# m303-stereo-output.net
KiCad netlist of a schematic drawn in EAGLE
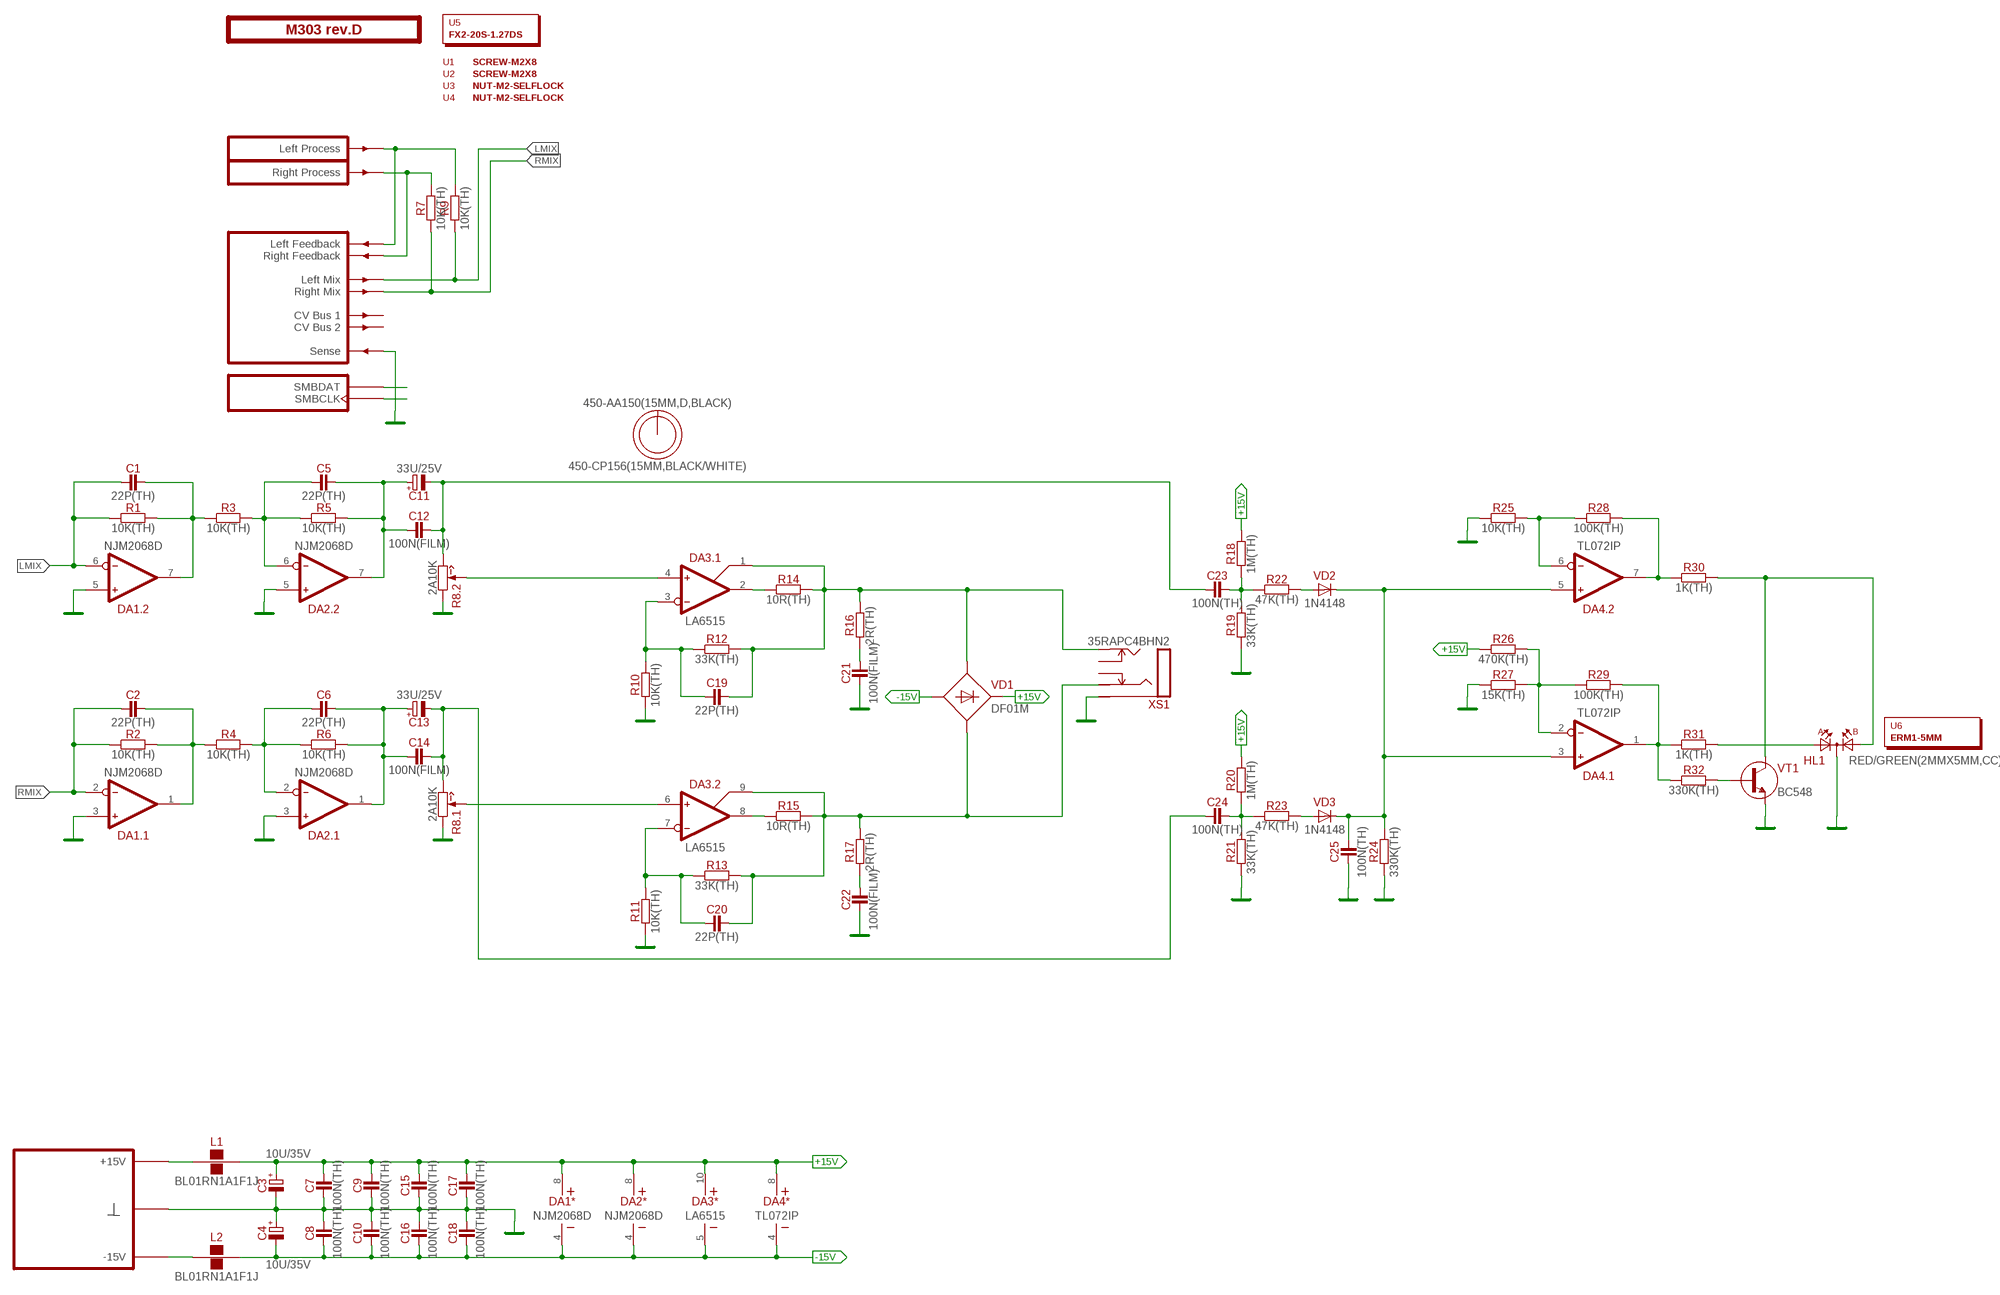
[diagram p0: schematic, sheet 1]

(export (version "E")
  (design (tool "Eeschema 10.0.6"))
  (components
    (comp (ref "C1")
      (value "22P(TH)")
      (footprint "eagle-import:C050-024X044")
      (libsource (lib "eagle-import") (part "?22P(TH)"))
    )
    (comp (ref "C2")
      (value "22P(TH)")
      (footprint "eagle-import:C050-024X044")
      (libsource (lib "eagle-import") (part "?22P(TH)"))
    )
    (comp (ref "C3")
      (value "10U/35V")
      (footprint "eagle-import:E2-5")
      (libsource (lib "eagle-import") (part "?10U/35V"))
    )
    (comp (ref "C4")
      (value "10U/35V")
      (footprint "eagle-import:E2-5")
      (libsource (lib "eagle-import") (part "?10U/35V"))
    )
    (comp (ref "C5")
      (value "22P(TH)")
      (footprint "eagle-import:C050-024X044")
      (libsource (lib "eagle-import") (part "?22P(TH)"))
    )
    (comp (ref "C6")
      (value "22P(TH)")
      (footprint "eagle-import:C050-024X044")
      (libsource (lib "eagle-import") (part "?22P(TH)"))
    )
    (comp (ref "C7")
      (value "100N(TH)")
      (footprint "eagle-import:C050-024X044")
      (libsource (lib "eagle-import") (part "?100N(TH)"))
    )
    (comp (ref "C8")
      (value "100N(TH)")
      (footprint "eagle-import:C050-024X044")
      (libsource (lib "eagle-import") (part "?100N(TH)"))
    )
    (comp (ref "C9")
      (value "100N(TH)")
      (footprint "eagle-import:C050-024X044")
      (libsource (lib "eagle-import") (part "?100N(TH)"))
    )
    (comp (ref "C10")
      (value "100N(TH)")
      (footprint "eagle-import:C050-024X044")
      (libsource (lib "eagle-import") (part "?100N(TH)"))
    )
    (comp (ref "C11")
      (value "33U/25V")
      (footprint "eagle-import:E2,5-7")
      (libsource (lib "eagle-import") (part "?33U/25V"))
    )
    (comp (ref "C12")
      (value "100N(FILM)")
      (footprint "eagle-import:C050-025X075")
      (libsource (lib "eagle-import") (part "?100N(FILM)"))
    )
    (comp (ref "C13")
      (value "33U/25V")
      (footprint "eagle-import:E2,5-7")
      (libsource (lib "eagle-import") (part "?33U/25V"))
    )
    (comp (ref "C14")
      (value "100N(FILM)")
      (footprint "eagle-import:C050-025X075")
      (libsource (lib "eagle-import") (part "?100N(FILM)"))
    )
    (comp (ref "C15")
      (value "100N(TH)")
      (footprint "eagle-import:C050-024X044")
      (libsource (lib "eagle-import") (part "?100N(TH)"))
    )
    (comp (ref "C16")
      (value "100N(TH)")
      (footprint "eagle-import:C050-024X044")
      (libsource (lib "eagle-import") (part "?100N(TH)"))
    )
    (comp (ref "C17")
      (value "100N(TH)")
      (footprint "eagle-import:C050-024X044")
      (libsource (lib "eagle-import") (part "?100N(TH)"))
    )
    (comp (ref "C18")
      (value "100N(TH)")
      (footprint "eagle-import:C050-024X044")
      (libsource (lib "eagle-import") (part "?100N(TH)"))
    )
    (comp (ref "C19")
      (value "22P(TH)")
      (footprint "eagle-import:C050-024X044")
      (libsource (lib "eagle-import") (part "?22P(TH)"))
    )
    (comp (ref "C20")
      (value "22P(TH)")
      (footprint "eagle-import:C050-024X044")
      (libsource (lib "eagle-import") (part "?22P(TH)"))
    )
    (comp (ref "C21")
      (value "100N(FILM)")
      (footprint "eagle-import:C050-025X075")
      (libsource (lib "eagle-import") (part "?100N(FILM)"))
    )
    (comp (ref "C22")
      (value "100N(FILM)")
      (footprint "eagle-import:C050-025X075")
      (libsource (lib "eagle-import") (part "?100N(FILM)"))
    )
    (comp (ref "C23")
      (value "100N(TH)")
      (footprint "eagle-import:C050-024X044")
      (libsource (lib "eagle-import") (part "?100N(TH)"))
    )
    (comp (ref "C24")
      (value "100N(TH)")
      (footprint "eagle-import:C050-024X044")
      (libsource (lib "eagle-import") (part "?100N(TH)"))
    )
    (comp (ref "C25")
      (value "100N(TH)")
      (footprint "eagle-import:C050-024X044")
      (libsource (lib "eagle-import") (part "?100N(TH)"))
    )
    (comp (ref "DA1")
      (value "NJM2068D")
      (footprint "eagle-import:DIP-8")
      (libsource (lib "eagle-import") (part "NJM2068D"))
    )
    (comp (ref "DA2")
      (value "NJM2068D")
      (footprint "eagle-import:DIP-8")
      (libsource (lib "eagle-import") (part "NJM2068D"))
    )
    (comp (ref "DA3")
      (value "LA6515")
      (footprint "eagle-import:SIL10")
      (libsource (lib "eagle-import") (part "LA6515"))
    )
    (comp (ref "DA4")
      (value "TL072IP")
      (footprint "eagle-import:DIP-8")
      (libsource (lib "eagle-import") (part "TL072IP"))
    )
    (comp (ref "HL1")
      (value "RED/GREEN(2MMX5MM,CC)")
      (footprint "eagle-import:LED2X5-3PIN")
      (libsource (lib "eagle-import") (part "?(2MMX5MM,CC)RED/GREEN"))
    )
    (comp (ref "L1")
      (value "BL01RN1A1F1J")
      (footprint "eagle-import:BL01RN1A")
      (libsource (lib "eagle-import") (part "BL01RN1A?1F1J"))
    )
    (comp (ref "L2")
      (value "BL01RN1A1F1J")
      (footprint "eagle-import:BL01RN1A")
      (libsource (lib "eagle-import") (part "BL01RN1A?1F1J"))
    )
    (comp (ref "O1")
      (value "450-AA150(15MM,D,BLACK)")
      (footprint "eagle-import:EMPTY")
      (libsource (lib "eagle-import") (part "450-AA?150(15MM,D,BLACK)"))
    )
    (comp (ref "O2")
      (value "450-CP156(15MM,BLACK/WHITE)")
      (footprint "eagle-import:EMPTY")
      (libsource (lib "eagle-import") (part "450-C?P156(15MM,BLACK/WHITE)"))
    )
    (comp (ref "PCB1")
      (value "M303 rev.D")
      (footprint "eagle-import:ST2-BOARD-50-END")
      (libsource (lib "eagle-import") (part "ST2-BOARD-50-END"))
    )
    (comp (ref "R1")
      (value "10K(TH)")
      (footprint "eagle-import:R-0207_10")
      (libsource (lib "eagle-import") (part "?10K(TH)"))
    )
    (comp (ref "R2")
      (value "10K(TH)")
      (footprint "eagle-import:R-0207_10")
      (libsource (lib "eagle-import") (part "?10K(TH)"))
    )
    (comp (ref "R3")
      (value "10K(TH)")
      (footprint "eagle-import:R-0207_10")
      (libsource (lib "eagle-import") (part "?10K(TH)"))
    )
    (comp (ref "R4")
      (value "10K(TH)")
      (footprint "eagle-import:R-0207_10")
      (libsource (lib "eagle-import") (part "?10K(TH)"))
    )
    (comp (ref "R5")
      (value "10K(TH)")
      (footprint "eagle-import:R-0207_10")
      (libsource (lib "eagle-import") (part "?10K(TH)"))
    )
    (comp (ref "R6")
      (value "10K(TH)")
      (footprint "eagle-import:R-0207_10")
      (libsource (lib "eagle-import") (part "?10K(TH)"))
    )
    (comp (ref "R7")
      (value "10K(TH)")
      (footprint "eagle-import:R-0207_10")
      (libsource (lib "eagle-import") (part "?10K(TH)"))
    )
    (comp (ref "R8")
      (value "2A10K")
      (footprint "eagle-import:RV11-DUAL")
      (libsource (lib "eagle-import") (part "2?A10K"))
    )
    (comp (ref "R9")
      (value "10K(TH)")
      (footprint "eagle-import:R-0207_10")
      (libsource (lib "eagle-import") (part "?10K(TH)"))
    )
    (comp (ref "R10")
      (value "10K(TH)")
      (footprint "eagle-import:R-0207_10")
      (libsource (lib "eagle-import") (part "?10K(TH)"))
    )
    (comp (ref "R11")
      (value "10K(TH)")
      (footprint "eagle-import:R-0207_10")
      (libsource (lib "eagle-import") (part "?10K(TH)"))
    )
    (comp (ref "R12")
      (value "33K(TH)")
      (footprint "eagle-import:R-0207_10")
      (libsource (lib "eagle-import") (part "?33K(TH)"))
    )
    (comp (ref "R13")
      (value "33K(TH)")
      (footprint "eagle-import:R-0207_10")
      (libsource (lib "eagle-import") (part "?33K(TH)"))
    )
    (comp (ref "R14")
      (value "10R(TH)")
      (footprint "eagle-import:R-0207_10")
      (libsource (lib "eagle-import") (part "?10R(TH)"))
    )
    (comp (ref "R15")
      (value "10R(TH)")
      (footprint "eagle-import:R-0207_10")
      (libsource (lib "eagle-import") (part "?10R(TH)"))
    )
    (comp (ref "R16")
      (value "2R(TH)")
      (footprint "eagle-import:R-0207_10")
      (libsource (lib "eagle-import") (part "?2R(TH)"))
    )
    (comp (ref "R17")
      (value "2R(TH)")
      (footprint "eagle-import:R-0207_10")
      (libsource (lib "eagle-import") (part "?2R(TH)"))
    )
    (comp (ref "R18")
      (value "1M(TH)")
      (footprint "eagle-import:R-0207_10")
      (libsource (lib "eagle-import") (part "?1M(TH)"))
    )
    (comp (ref "R19")
      (value "33K(TH)")
      (footprint "eagle-import:R-0207_10")
      (libsource (lib "eagle-import") (part "?33K(TH)"))
    )
    (comp (ref "R20")
      (value "1M(TH)")
      (footprint "eagle-import:R-0207_10")
      (libsource (lib "eagle-import") (part "?1M(TH)"))
    )
    (comp (ref "R21")
      (value "33K(TH)")
      (footprint "eagle-import:R-0207_10")
      (libsource (lib "eagle-import") (part "?33K(TH)"))
    )
    (comp (ref "R22")
      (value "47K(TH)")
      (footprint "eagle-import:R-0207_10")
      (libsource (lib "eagle-import") (part "?47K(TH)"))
    )
    (comp (ref "R23")
      (value "47K(TH)")
      (footprint "eagle-import:R-0207_10")
      (libsource (lib "eagle-import") (part "?47K(TH)"))
    )
    (comp (ref "R24")
      (value "330K(TH)")
      (footprint "eagle-import:R-0207_10")
      (libsource (lib "eagle-import") (part "?330K(TH)"))
    )
    (comp (ref "R25")
      (value "10K(TH)")
      (footprint "eagle-import:R-0207_10")
      (libsource (lib "eagle-import") (part "?10K(TH)"))
    )
    (comp (ref "R26")
      (value "470K(TH)")
      (footprint "eagle-import:R-0207_10")
      (libsource (lib "eagle-import") (part "?470K(TH)"))
    )
    (comp (ref "R27")
      (value "15K(TH)")
      (footprint "eagle-import:R-0207_10")
      (libsource (lib "eagle-import") (part "?15K(TH)"))
    )
    (comp (ref "R28")
      (value "100K(TH)")
      (footprint "eagle-import:R-0207_10")
      (libsource (lib "eagle-import") (part "?100K(TH)"))
    )
    (comp (ref "R29")
      (value "100K(TH)")
      (footprint "eagle-import:R-0207_10")
      (libsource (lib "eagle-import") (part "?100K(TH)"))
    )
    (comp (ref "R30")
      (value "1K(TH)")
      (footprint "eagle-import:R-0207_10")
      (libsource (lib "eagle-import") (part "?1K(TH)"))
    )
    (comp (ref "R31")
      (value "1K(TH)")
      (footprint "eagle-import:R-0207_10")
      (libsource (lib "eagle-import") (part "?1K(TH)"))
    )
    (comp (ref "R32")
      (value "330K(TH)")
      (footprint "eagle-import:R-0207_10")
      (libsource (lib "eagle-import") (part "?330K(TH)"))
    )
    (comp (ref "U1")
      (value "SCREW-M2X8")
      (footprint "eagle-import:EMPTY")
      (libsource (lib "eagle-import") (part "?SCREW-M2X8"))
    )
    (comp (ref "U2")
      (value "SCREW-M2X8")
      (footprint "eagle-import:EMPTY")
      (libsource (lib "eagle-import") (part "?SCREW-M2X8"))
    )
    (comp (ref "U3")
      (value "NUT-M2-SELFLOCK")
      (footprint "eagle-import:EMPTY")
      (libsource (lib "eagle-import") (part "?NUT-M2-SELFLOCK"))
    )
    (comp (ref "U4")
      (value "NUT-M2-SELFLOCK")
      (footprint "eagle-import:EMPTY")
      (libsource (lib "eagle-import") (part "?NUT-M2-SELFLOCK"))
    )
    (comp (ref "U5")
      (value "FX2-20S-1.27DS")
      (footprint "eagle-import:EMPTY")
      (libsource (lib "eagle-import") (part "?FX2-20S-1.27DS"))
    )
    (comp (ref "U6")
      (value "ERM1-5MM")
      (footprint "eagle-import:EMPTY")
      (libsource (lib "eagle-import") (part "?ERM1-5MM"))
    )
    (comp (ref "VD1")
      (value "DF01M")
      (footprint "eagle-import:MDIP-4")
      (libsource (lib "eagle-import") (part "DF?M01"))
    )
    (comp (ref "VD2")
      (value "1N4148")
      (footprint "eagle-import:DO35-7")
      (libsource (lib "eagle-import") (part "?1N4148"))
    )
    (comp (ref "VD3")
      (value "1N4148")
      (footprint "eagle-import:DO35-7")
      (libsource (lib "eagle-import") (part "?1N4148"))
    )
    (comp (ref "VT1")
      (value "BC548")
      (footprint "eagle-import:TO92")
      (libsource (lib "eagle-import") (part "?BC548"))
    )
    (comp (ref "XS1")
      (value "35RAPC4BHN2")
      (footprint "eagle-import:35RAP")
      (libsource (lib "eagle-import") (part "35RAPC4BHN2"))
    )
  )
  (nets
    (net (code "1") (name "+15V") (class "Default")
      (node (ref "C15") (pin "2") (pinfunction "2_2") (pintype "passive"))
      (node (ref "C17") (pin "2") (pinfunction "2_2") (pintype "passive"))
      (node (ref "C3") (pin "+") (pinfunction "+_+") (pintype "passive"))
      (node (ref "C7") (pin "2") (pinfunction "2_2") (pintype "passive"))
      (node (ref "C9") (pin "2") (pinfunction "2_2") (pintype "passive"))
      (node (ref "DA1") (pin "8") (pinfunction "V+_8") (pintype "power_in"))
      (node (ref "DA2") (pin "8") (pinfunction "V+_8") (pintype "power_in"))
      (node (ref "DA3") (pin "10") (pinfunction "V+_10") (pintype "power_in"))
      (node (ref "DA4") (pin "8") (pinfunction "V+_8") (pintype "power_in"))
      (node (ref "L1") (pin "2") (pinfunction "2_2") (pintype "passive"))
      (node (ref "R18") (pin "2") (pinfunction "2_2") (pintype "passive"))
      (node (ref "R20") (pin "2") (pinfunction "2_2") (pintype "passive"))
      (node (ref "R26") (pin "1") (pinfunction "1_1") (pintype "passive"))
      (node (ref "VD1") (pin "3") (pinfunction "C_3") (pintype "passive"))
    )
    (net (code "2") (name "-15V") (class "Default")
      (node (ref "C10") (pin "1") (pinfunction "1_1") (pintype "passive"))
      (node (ref "C16") (pin "1") (pinfunction "1_1") (pintype "passive"))
      (node (ref "C18") (pin "1") (pinfunction "1_1") (pintype "passive"))
      (node (ref "C4") (pin "-") (pinfunction "-_-") (pintype "passive"))
      (node (ref "C8") (pin "1") (pinfunction "1_1") (pintype "passive"))
      (node (ref "DA1") (pin "4") (pinfunction "V-_4") (pintype "power_in"))
      (node (ref "DA2") (pin "4") (pinfunction "V-_4") (pintype "power_in"))
      (node (ref "DA3") (pin "5") (pinfunction "V-_5") (pintype "power_in"))
      (node (ref "DA4") (pin "4") (pinfunction "V-_4") (pintype "power_in"))
      (node (ref "L2") (pin "2") (pinfunction "2_2") (pintype "passive"))
      (node (ref "VD1") (pin "4") (pinfunction "A_4") (pintype "passive"))
    )
    (net (code "3") (name "GND") (class "Default")
      (node (ref "C10") (pin "2") (pinfunction "2_2") (pintype "passive"))
      (node (ref "C15") (pin "1") (pinfunction "1_1") (pintype "passive"))
      (node (ref "C16") (pin "2") (pinfunction "2_2") (pintype "passive"))
      (node (ref "C17") (pin "1") (pinfunction "1_1") (pintype "passive"))
      (node (ref "C18") (pin "2") (pinfunction "2_2") (pintype "passive"))
      (node (ref "C21") (pin "1") (pinfunction "1_1") (pintype "passive"))
      (node (ref "C22") (pin "1") (pinfunction "1_1") (pintype "passive"))
      (node (ref "C25") (pin "1") (pinfunction "1_1") (pintype "passive"))
      (node (ref "C3") (pin "-") (pinfunction "-_-") (pintype "passive"))
      (node (ref "C4") (pin "+") (pinfunction "+_+") (pintype "passive"))
      (node (ref "C7") (pin "1") (pinfunction "1_1") (pintype "passive"))
      (node (ref "C8") (pin "2") (pinfunction "2_2") (pintype "passive"))
      (node (ref "C9") (pin "1") (pinfunction "1_1") (pintype "passive"))
      (node (ref "DA1") (pin "3") (pinfunction "IN+_3") (pintype "input"))
      (node (ref "DA1") (pin "5") (pinfunction "IN+_5") (pintype "input"))
      (node (ref "DA2") (pin "3") (pinfunction "IN+_3") (pintype "input"))
      (node (ref "DA2") (pin "5") (pinfunction "IN+_5") (pintype "input"))
      (node (ref "HL1") (pin "K") (pinfunction "K_K") (pintype "passive"))
      (node (ref "PCB1") (pin "B4") (pinfunction "GND_B4") (pintype "bidirectional"))
      (node (ref "PCB1") (pin "B5") (pinfunction "GND_B5") (pintype "bidirectional"))
      (node (ref "PCB1") (pin "B6") (pinfunction "GND_B6") (pintype "bidirectional"))
      (node (ref "PCB1") (pin "B7") (pinfunction "GND_B7") (pintype "bidirectional"))
      (node (ref "PCB1") (pin "B8") (pinfunction "GND_B8") (pintype "bidirectional"))
      (node (ref "PCB1") (pin "BSENSE") (pinfunction "SENSE_BSENSE") (pintype "bidirectional"))
      (node (ref "R10") (pin "1") (pinfunction "1_1") (pintype "passive"))
      (node (ref "R11") (pin "1") (pinfunction "1_1") (pintype "passive"))
      (node (ref "R19") (pin "1") (pinfunction "1_1") (pintype "passive"))
      (node (ref "R21") (pin "1") (pinfunction "1_1") (pintype "passive"))
      (node (ref "R24") (pin "1") (pinfunction "1_1") (pintype "passive"))
      (node (ref "R25") (pin "1") (pinfunction "1_1") (pintype "passive"))
      (node (ref "R27") (pin "1") (pinfunction "1_1") (pintype "passive"))
      (node (ref "R8") (pin "1") (pinfunction "CCW_1") (pintype "passive"))
      (node (ref "R8") (pin "1'") (pinfunction "CCW_1'") (pintype "passive"))
      (node (ref "VT1") (pin "3") (pinfunction "E_3") (pintype "passive"))
      (node (ref "XS1") (pin "1") (pinfunction "S_1") (pintype "passive"))
    )
    (net (code "4") (name "LMIX") (class "Default")
      (node (ref "C1") (pin "1") (pinfunction "1_1") (pintype "passive"))
      (node (ref "DA1") (pin "6") (pinfunction "IN-_6") (pintype "input"))
      (node (ref "PCB1") (pin "ALMIX") (pinfunction "LMIX_ALMIX") (pintype "bidirectional"))
      (node (ref "R1") (pin "1") (pinfunction "1_1") (pintype "passive"))
      (node (ref "R9") (pin "1") (pinfunction "1_1") (pintype "passive"))
    )
    (net (code "5") (name "Net-(C21-Pad2)") (class "Default")
      (node (ref "C21") (pin "2") (pinfunction "2_2") (pintype "passive"))
      (node (ref "R16") (pin "1") (pinfunction "1_1") (pintype "passive"))
    )
    (net (code "6") (name "Net-(C22-Pad2)") (class "Default")
      (node (ref "C22") (pin "2") (pinfunction "2_2") (pintype "passive"))
      (node (ref "R17") (pin "1") (pinfunction "1_1") (pintype "passive"))
    )
    (net (code "7") (name "Net-(C23-Pad2)") (class "Default")
      (node (ref "C23") (pin "2") (pinfunction "2_2") (pintype "passive"))
      (node (ref "R18") (pin "1") (pinfunction "1_1") (pintype "passive"))
      (node (ref "R19") (pin "2") (pinfunction "2_2") (pintype "passive"))
      (node (ref "R22") (pin "1") (pinfunction "1_1") (pintype "passive"))
    )
    (net (code "8") (name "Net-(C24-Pad2)") (class "Default")
      (node (ref "C24") (pin "2") (pinfunction "2_2") (pintype "passive"))
      (node (ref "R20") (pin "1") (pinfunction "1_1") (pintype "passive"))
      (node (ref "R21") (pin "2") (pinfunction "2_2") (pintype "passive"))
      (node (ref "R23") (pin "1") (pinfunction "1_1") (pintype "passive"))
    )
    (net (code "9") (name "Net-(DA1B-OUT)") (class "Default")
      (node (ref "C2") (pin "2") (pinfunction "2_2") (pintype "passive"))
      (node (ref "DA1") (pin "1") (pinfunction "OUT_1") (pintype "output"))
      (node (ref "R2") (pin "2") (pinfunction "2_2") (pintype "passive"))
      (node (ref "R4") (pin "1") (pinfunction "1_1") (pintype "passive"))
    )
    (net (code "10") (name "Net-(DA1C-OUT)") (class "Default")
      (node (ref "C1") (pin "2") (pinfunction "2_2") (pintype "passive"))
      (node (ref "DA1") (pin "7") (pinfunction "OUT_7") (pintype "output"))
      (node (ref "R1") (pin "2") (pinfunction "2_2") (pintype "passive"))
      (node (ref "R3") (pin "1") (pinfunction "1_1") (pintype "passive"))
    )
    (net (code "11") (name "Net-(DA2B-IN-)") (class "Default")
      (node (ref "C6") (pin "1") (pinfunction "1_1") (pintype "passive"))
      (node (ref "DA2") (pin "2") (pinfunction "IN-_2") (pintype "input"))
      (node (ref "R4") (pin "2") (pinfunction "2_2") (pintype "passive"))
      (node (ref "R6") (pin "1") (pinfunction "1_1") (pintype "passive"))
    )
    (net (code "12") (name "Net-(DA2B-OUT)") (class "Default")
      (node (ref "C13") (pin "+") (pinfunction "+_+") (pintype "passive"))
      (node (ref "C14") (pin "1") (pinfunction "1_1") (pintype "passive"))
      (node (ref "C6") (pin "2") (pinfunction "2_2") (pintype "passive"))
      (node (ref "DA2") (pin "1") (pinfunction "OUT_1") (pintype "output"))
      (node (ref "R6") (pin "2") (pinfunction "2_2") (pintype "passive"))
    )
    (net (code "13") (name "Net-(DA2C-IN-)") (class "Default")
      (node (ref "C5") (pin "1") (pinfunction "1_1") (pintype "passive"))
      (node (ref "DA2") (pin "6") (pinfunction "IN-_6") (pintype "input"))
      (node (ref "R3") (pin "2") (pinfunction "2_2") (pintype "passive"))
      (node (ref "R5") (pin "1") (pinfunction "1_1") (pintype "passive"))
    )
    (net (code "14") (name "Net-(DA2C-OUT)") (class "Default")
      (node (ref "C11") (pin "+") (pinfunction "+_+") (pintype "passive"))
      (node (ref "C12") (pin "1") (pinfunction "1_1") (pintype "passive"))
      (node (ref "C5") (pin "2") (pinfunction "2_2") (pintype "passive"))
      (node (ref "DA2") (pin "7") (pinfunction "OUT_7") (pintype "output"))
      (node (ref "R5") (pin "2") (pinfunction "2_2") (pintype "passive"))
    )
    (net (code "15") (name "Net-(DA3B-IN+)") (class "Default")
      (node (ref "DA3") (pin "4") (pinfunction "IN+_4") (pintype "input"))
      (node (ref "R8") (pin "2'") (pinfunction "W_2'") (pintype "passive"))
    )
    (net (code "16") (name "Net-(DA3B-IN-)") (class "Default")
      (node (ref "C19") (pin "1") (pinfunction "1_1") (pintype "passive"))
      (node (ref "DA3") (pin "3") (pinfunction "IN-_3") (pintype "input"))
      (node (ref "R10") (pin "2") (pinfunction "2_2") (pintype "passive"))
      (node (ref "R12") (pin "1") (pinfunction "1_1") (pintype "passive"))
    )
    (net (code "17") (name "Net-(DA3B-OUT)") (class "Default")
      (node (ref "DA3") (pin "2") (pinfunction "OUT_2") (pintype "output"))
      (node (ref "R14") (pin "1") (pinfunction "1_1") (pintype "passive"))
    )
    (net (code "18") (name "Net-(DA3B-SENSE)") (class "Default")
      (node (ref "C19") (pin "2") (pinfunction "2_2") (pintype "passive"))
      (node (ref "DA3") (pin "1") (pinfunction "SENSE_1") (pintype "output"))
      (node (ref "R12") (pin "2") (pinfunction "2_2") (pintype "passive"))
      (node (ref "R14") (pin "2") (pinfunction "2_2") (pintype "passive"))
      (node (ref "R16") (pin "2") (pinfunction "2_2") (pintype "passive"))
      (node (ref "VD1") (pin "1") (pinfunction "AC1_1") (pintype "passive"))
      (node (ref "XS1") (pin "2") (pinfunction "T_2") (pintype "passive"))
    )
    (net (code "19") (name "Net-(DA3C-IN+)") (class "Default")
      (node (ref "DA3") (pin "6") (pinfunction "IN+_6") (pintype "input"))
      (node (ref "R8") (pin "2") (pinfunction "W_2") (pintype "passive"))
    )
    (net (code "20") (name "Net-(DA3C-IN-)") (class "Default")
      (node (ref "C20") (pin "1") (pinfunction "1_1") (pintype "passive"))
      (node (ref "DA3") (pin "7") (pinfunction "IN-_7") (pintype "input"))
      (node (ref "R11") (pin "2") (pinfunction "2_2") (pintype "passive"))
      (node (ref "R13") (pin "1") (pinfunction "1_1") (pintype "passive"))
    )
    (net (code "21") (name "Net-(DA3C-OUT)") (class "Default")
      (node (ref "DA3") (pin "8") (pinfunction "OUT_8") (pintype "output"))
      (node (ref "R15") (pin "1") (pinfunction "1_1") (pintype "passive"))
    )
    (net (code "22") (name "Net-(DA3C-SENSE)") (class "Default")
      (node (ref "C20") (pin "2") (pinfunction "2_2") (pintype "passive"))
      (node (ref "DA3") (pin "9") (pinfunction "SENSE_9") (pintype "output"))
      (node (ref "R13") (pin "2") (pinfunction "2_2") (pintype "passive"))
      (node (ref "R15") (pin "2") (pinfunction "2_2") (pintype "passive"))
      (node (ref "R17") (pin "2") (pinfunction "2_2") (pintype "passive"))
      (node (ref "VD1") (pin "2") (pinfunction "AC2_2") (pintype "passive"))
      (node (ref "XS1") (pin "3") (pinfunction "R_3") (pintype "passive"))
    )
    (net (code "23") (name "Net-(DA4B-IN+)") (class "Default")
      (node (ref "C25") (pin "2") (pinfunction "2_2") (pintype "passive"))
      (node (ref "DA4") (pin "3") (pinfunction "IN+_3") (pintype "input"))
      (node (ref "DA4") (pin "5") (pinfunction "IN+_5") (pintype "input"))
      (node (ref "R24") (pin "2") (pinfunction "2_2") (pintype "passive"))
      (node (ref "VD2") (pin "C") (pinfunction "C_C") (pintype "passive"))
      (node (ref "VD3") (pin "C") (pinfunction "C_C") (pintype "passive"))
    )
    (net (code "24") (name "Net-(DA4B-IN-)") (class "Default")
      (node (ref "DA4") (pin "2") (pinfunction "IN-_2") (pintype "input"))
      (node (ref "R26") (pin "2") (pinfunction "2_2") (pintype "passive"))
      (node (ref "R27") (pin "2") (pinfunction "2_2") (pintype "passive"))
      (node (ref "R29") (pin "1") (pinfunction "1_1") (pintype "passive"))
    )
    (net (code "25") (name "Net-(DA4B-OUT)") (class "Default")
      (node (ref "DA4") (pin "1") (pinfunction "OUT_1") (pintype "output"))
      (node (ref "R29") (pin "2") (pinfunction "2_2") (pintype "passive"))
      (node (ref "R31") (pin "1") (pinfunction "1_1") (pintype "passive"))
      (node (ref "R32") (pin "1") (pinfunction "1_1") (pintype "passive"))
    )
    (net (code "26") (name "Net-(DA4C-IN-)") (class "Default")
      (node (ref "DA4") (pin "6") (pinfunction "IN-_6") (pintype "input"))
      (node (ref "R25") (pin "2") (pinfunction "2_2") (pintype "passive"))
      (node (ref "R28") (pin "1") (pinfunction "1_1") (pintype "passive"))
    )
    (net (code "27") (name "Net-(DA4C-OUT)") (class "Default")
      (node (ref "DA4") (pin "7") (pinfunction "OUT_7") (pintype "output"))
      (node (ref "R28") (pin "2") (pinfunction "2_2") (pintype "passive"))
      (node (ref "R30") (pin "1") (pinfunction "1_1") (pintype "passive"))
    )
    (net (code "28") (name "Net-(HL1-PadA1)") (class "Default")
      (node (ref "HL1") (pin "A1") (pinfunction "A1_A1") (pintype "passive"))
      (node (ref "R31") (pin "2") (pinfunction "2_2") (pintype "passive"))
    )
    (net (code "29") (name "Net-(L1-Pad1)") (class "Default")
      (node (ref "L1") (pin "1") (pinfunction "1_1") (pintype "passive"))
      (node (ref "PCB1") (pin "A+15") (pinfunction "P+15V_A+15") (pintype "bidirectional"))
      (node (ref "PCB1") (pin "B+15") (pinfunction "P+15V_B+15") (pintype "bidirectional"))
    )
    (net (code "30") (name "Net-(L2-Pad1)") (class "Default")
      (node (ref "L2") (pin "1") (pinfunction "1_1") (pintype "passive"))
      (node (ref "PCB1") (pin "A-15") (pinfunction "P-15V_A-15") (pintype "bidirectional"))
      (node (ref "PCB1") (pin "B-15") (pinfunction "P-15V_B-15") (pintype "bidirectional"))
    )
    (net (code "31") (name "Net-(PCB1B-INL)") (class "Default")
      (node (ref "PCB1") (pin "ALFBK") (pinfunction "LFBK_ALFBK") (pintype "bidirectional"))
      (node (ref "PCB1") (pin "BINL") (pinfunction "INL_BINL") (pintype "bidirectional"))
      (node (ref "R9") (pin "2") (pinfunction "2_2") (pintype "passive"))
    )
    (net (code "32") (name "Net-(PCB1C-INR)") (class "Default")
      (node (ref "PCB1") (pin "ARFBK") (pinfunction "RFBK_ARFBK") (pintype "bidirectional"))
      (node (ref "PCB1") (pin "BINR") (pinfunction "INR_BINR") (pintype "bidirectional"))
      (node (ref "R7") (pin "2") (pinfunction "2_2") (pintype "passive"))
    )
    (net (code "33") (name "Net-(R8A-CW)") (class "Default")
      (node (ref "C13") (pin "-") (pinfunction "-_-") (pintype "passive"))
      (node (ref "C14") (pin "2") (pinfunction "2_2") (pintype "passive"))
      (node (ref "C24") (pin "1") (pinfunction "1_1") (pintype "passive"))
      (node (ref "R8") (pin "3") (pinfunction "CW_3") (pintype "passive"))
    )
    (net (code "34") (name "Net-(R8B-CW)") (class "Default")
      (node (ref "C11") (pin "-") (pinfunction "-_-") (pintype "passive"))
      (node (ref "C12") (pin "2") (pinfunction "2_2") (pintype "passive"))
      (node (ref "C23") (pin "1") (pinfunction "1_1") (pintype "passive"))
      (node (ref "R8") (pin "3'") (pinfunction "CW_3'") (pintype "passive"))
    )
    (net (code "35") (name "Net-(R22-Pad2)") (class "Default")
      (node (ref "R22") (pin "2") (pinfunction "2_2") (pintype "passive"))
      (node (ref "VD2") (pin "A") (pinfunction "A_A") (pintype "passive"))
    )
    (net (code "36") (name "Net-(R23-Pad2)") (class "Default")
      (node (ref "R23") (pin "2") (pinfunction "2_2") (pintype "passive"))
      (node (ref "VD3") (pin "A") (pinfunction "A_A") (pintype "passive"))
    )
    (net (code "37") (name "Net-(VT1-B)") (class "Default")
      (node (ref "R32") (pin "2") (pinfunction "2_2") (pintype "passive"))
      (node (ref "VT1") (pin "2") (pinfunction "B_2") (pintype "passive"))
    )
    (net (code "38") (name "Net-(VT1-C)") (class "Default")
      (node (ref "HL1") (pin "A2") (pinfunction "A2_A2") (pintype "passive"))
      (node (ref "R30") (pin "2") (pinfunction "2_2") (pintype "passive"))
      (node (ref "VT1") (pin "1") (pinfunction "C_1") (pintype "passive"))
    )
    (net (code "39") (name "RMIX") (class "Default")
      (node (ref "C2") (pin "1") (pinfunction "1_1") (pintype "passive"))
      (node (ref "DA1") (pin "2") (pinfunction "IN-_2") (pintype "input"))
      (node (ref "PCB1") (pin "ARMIX") (pinfunction "RMIX_ARMIX") (pintype "bidirectional"))
      (node (ref "R2") (pin "1") (pinfunction "1_1") (pintype "passive"))
      (node (ref "R7") (pin "1") (pinfunction "1_1") (pintype "passive"))
    )
    (net (code "40") (name "unconnected-(PCB1D-CV1-PadACV1)") (class "Default")
      (node (ref "PCB1") (pin "ACV1") (pinfunction "CV1_ACV1") (pintype "bidirectional"))
    )
    (net (code "41") (name "unconnected-(PCB1D-CV2-PadACV2)") (class "Default")
      (node (ref "PCB1") (pin "ACV2") (pinfunction "CV2_ACV2") (pintype "bidirectional"))
    )
    (net (code "42") (name "unconnected-(PCB1E-SMBCLK-PadASMBCLK)") (class "Default")
      (node (ref "PCB1") (pin "ASMBCLK") (pinfunction "SMBCLK_ASMBCLK") (pintype "bidirectional"))
    )
    (net (code "43") (name "unconnected-(PCB1E-SMBDAT-PadASMBDAT)") (class "Default")
      (node (ref "PCB1") (pin "ASMBDAT") (pinfunction "SMBDAT_ASMBDAT") (pintype "bidirectional"))
    )
    (net (code "44") (name "unconnected-(XS1-RN-Pad11)") (class "Default")
      (node (ref "XS1") (pin "11") (pinfunction "RN_11") (pintype "passive"))
    )
    (net (code "45") (name "unconnected-(XS1-TN-Pad10)") (class "Default")
      (node (ref "XS1") (pin "10") (pinfunction "TN_10") (pintype "passive"))
    )
  )
)
